# LED_String_NE2R757GT-P6.net
KiCad netlist of a schematic drawn in Altium Designer
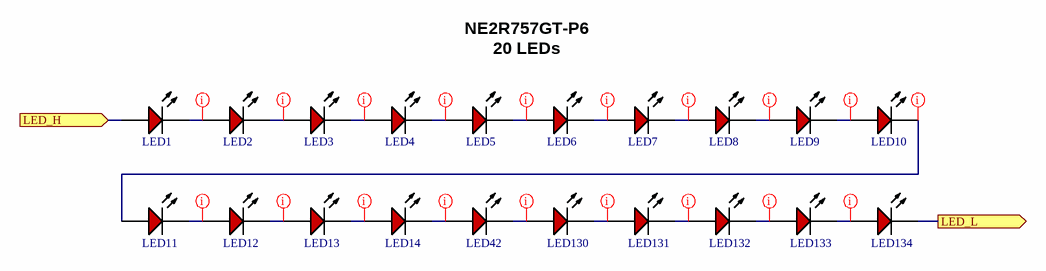
[diagram p0: LED_String_NE2R757GT-P6.SchDoc]

(export (version "E")
  (design (tool "Eeschema 10.0.6"))
  (components
    (comp (ref "LED1")
      (value "NE2R757GT-P6")
      (footprint "NE2R757GT-P6")
      (description "SMD LED Red 2,13 V, 16 lm 3030 (1212)")
      (fields (field (name "MANUFACTURER") "Nichia"))
      (libsource (lib "ETHZ Vault") (part "LED Red"))
    )
    (comp (ref "LED2")
      (value "NE2R757GT-P6")
      (footprint "NE2R757GT-P6")
      (description "SMD LED Red 2,13 V, 16 lm 3030 (1212)")
      (fields (field (name "MANUFACTURER") "Nichia"))
      (libsource (lib "ETHZ Vault") (part "LED Red"))
    )
    (comp (ref "LED3")
      (value "NE2R757GT-P6")
      (footprint "NE2R757GT-P6")
      (description "SMD LED Red 2,13 V, 16 lm 3030 (1212)")
      (fields (field (name "MANUFACTURER") "Nichia"))
      (libsource (lib "ETHZ Vault") (part "LED Red"))
    )
    (comp (ref "LED4")
      (value "NE2R757GT-P6")
      (footprint "NE2R757GT-P6")
      (description "SMD LED Red 2,13 V, 16 lm 3030 (1212)")
      (fields (field (name "MANUFACTURER") "Nichia"))
      (libsource (lib "ETHZ Vault") (part "LED Red"))
    )
    (comp (ref "LED5")
      (value "NE2R757GT-P6")
      (footprint "NE2R757GT-P6")
      (description "SMD LED Red 2,13 V, 16 lm 3030 (1212)")
      (fields (field (name "MANUFACTURER") "Nichia"))
      (libsource (lib "ETHZ Vault") (part "LED Red"))
    )
    (comp (ref "LED6")
      (value "NE2R757GT-P6")
      (footprint "NE2R757GT-P6")
      (description "SMD LED Red 2,13 V, 16 lm 3030 (1212)")
      (fields (field (name "MANUFACTURER") "Nichia"))
      (libsource (lib "ETHZ Vault") (part "LED Red"))
    )
    (comp (ref "LED7")
      (value "NE2R757GT-P6")
      (footprint "NE2R757GT-P6")
      (description "SMD LED Red 2,13 V, 16 lm 3030 (1212)")
      (fields (field (name "MANUFACTURER") "Nichia"))
      (libsource (lib "ETHZ Vault") (part "LED Red"))
    )
    (comp (ref "LED8")
      (value "NE2R757GT-P6")
      (footprint "NE2R757GT-P6")
      (description "SMD LED Red 2,13 V, 16 lm 3030 (1212)")
      (fields (field (name "MANUFACTURER") "Nichia"))
      (libsource (lib "ETHZ Vault") (part "LED Red"))
    )
    (comp (ref "LED9")
      (value "NE2R757GT-P6")
      (footprint "NE2R757GT-P6")
      (description "SMD LED Red 2,13 V, 16 lm 3030 (1212)")
      (fields (field (name "MANUFACTURER") "Nichia"))
      (libsource (lib "ETHZ Vault") (part "LED Red"))
    )
    (comp (ref "LED10")
      (value "NE2R757GT-P6")
      (footprint "NE2R757GT-P6")
      (description "SMD LED Red 2,13 V, 16 lm 3030 (1212)")
      (fields (field (name "MANUFACTURER") "Nichia"))
      (libsource (lib "ETHZ Vault") (part "LED Red"))
    )
    (comp (ref "LED11")
      (value "NE2R757GT-P6")
      (footprint "NE2R757GT-P6")
      (description "SMD LED Red 2,13 V, 16 lm 3030 (1212)")
      (fields (field (name "MANUFACTURER") "Nichia"))
      (libsource (lib "ETHZ Vault") (part "LED Red"))
    )
    (comp (ref "LED12")
      (value "NE2R757GT-P6")
      (footprint "NE2R757GT-P6")
      (description "SMD LED Red 2,13 V, 16 lm 3030 (1212)")
      (fields (field (name "MANUFACTURER") "Nichia"))
      (libsource (lib "ETHZ Vault") (part "LED Red"))
    )
    (comp (ref "LED13")
      (value "NE2R757GT-P6")
      (footprint "NE2R757GT-P6")
      (description "SMD LED Red 2,13 V, 16 lm 3030 (1212)")
      (fields (field (name "MANUFACTURER") "Nichia"))
      (libsource (lib "ETHZ Vault") (part "LED Red"))
    )
    (comp (ref "LED14")
      (value "NE2R757GT-P6")
      (footprint "NE2R757GT-P6")
      (description "SMD LED Red 2,13 V, 16 lm 3030 (1212)")
      (fields (field (name "MANUFACTURER") "Nichia"))
      (libsource (lib "ETHZ Vault") (part "LED Red"))
    )
    (comp (ref "LED42")
      (value "NE2R757GT-P6")
      (footprint "NE2R757GT-P6")
      (description "SMD LED Red 2,13 V, 16 lm 3030 (1212)")
      (fields (field (name "MANUFACTURER") "Nichia"))
      (libsource (lib "ETHZ Vault") (part "LED Red"))
    )
    (comp (ref "LED130")
      (value "NE2R757GT-P6")
      (footprint "NE2R757GT-P6")
      (description "SMD LED Red 2,13 V, 16 lm 3030 (1212)")
      (fields (field (name "MANUFACTURER") "Nichia"))
      (libsource (lib "ETHZ Vault") (part "LED Red"))
    )
    (comp (ref "LED131")
      (value "NE2R757GT-P6")
      (footprint "NE2R757GT-P6")
      (description "SMD LED Red 2,13 V, 16 lm 3030 (1212)")
      (fields (field (name "MANUFACTURER") "Nichia"))
      (libsource (lib "ETHZ Vault") (part "LED Red"))
    )
    (comp (ref "LED132")
      (value "NE2R757GT-P6")
      (footprint "NE2R757GT-P6")
      (description "SMD LED Red 2,13 V, 16 lm 3030 (1212)")
      (fields (field (name "MANUFACTURER") "Nichia"))
      (libsource (lib "ETHZ Vault") (part "LED Red"))
    )
    (comp (ref "LED133")
      (value "NE2R757GT-P6")
      (footprint "NE2R757GT-P6")
      (description "SMD LED Red 2,13 V, 16 lm 3030 (1212)")
      (fields (field (name "MANUFACTURER") "Nichia"))
      (libsource (lib "ETHZ Vault") (part "LED Red"))
    )
    (comp (ref "LED134")
      (value "NE2R757GT-P6")
      (footprint "NE2R757GT-P6")
      (description "SMD LED Red 2,13 V, 16 lm 3030 (1212)")
      (fields (field (name "MANUFACTURER") "Nichia"))
      (libsource (lib "ETHZ Vault") (part "LED Red"))
    )
  )
  (nets
    (net (code "1") (name "/LED_H") (class "Default")
      (node (ref "LED1") (pin "2") (pinfunction "A_2") (pintype "passive"))
    )
    (net (code "2") (name "/LED_L") (class "Default")
      (node (ref "LED134") (pin "1") (pinfunction "K_1") (pintype "passive"))
    )
    (net (code "3") (name "Net-(LED1-K)") (class "Default")
      (node (ref "LED1") (pin "1") (pinfunction "K_1") (pintype "passive"))
      (node (ref "LED2") (pin "2") (pinfunction "A_2") (pintype "passive"))
    )
    (net (code "4") (name "Net-(LED2-K)") (class "Default")
      (node (ref "LED2") (pin "1") (pinfunction "K_1") (pintype "passive"))
      (node (ref "LED3") (pin "2") (pinfunction "A_2") (pintype "passive"))
    )
    (net (code "5") (name "Net-(LED3-K)") (class "Default")
      (node (ref "LED3") (pin "1") (pinfunction "K_1") (pintype "passive"))
      (node (ref "LED4") (pin "2") (pinfunction "A_2") (pintype "passive"))
    )
    (net (code "6") (name "Net-(LED4-K)") (class "Default")
      (node (ref "LED4") (pin "1") (pinfunction "K_1") (pintype "passive"))
      (node (ref "LED5") (pin "2") (pinfunction "A_2") (pintype "passive"))
    )
    (net (code "7") (name "Net-(LED5-K)") (class "Default")
      (node (ref "LED5") (pin "1") (pinfunction "K_1") (pintype "passive"))
      (node (ref "LED6") (pin "2") (pinfunction "A_2") (pintype "passive"))
    )
    (net (code "8") (name "Net-(LED6-K)") (class "Default")
      (node (ref "LED6") (pin "1") (pinfunction "K_1") (pintype "passive"))
      (node (ref "LED7") (pin "2") (pinfunction "A_2") (pintype "passive"))
    )
    (net (code "9") (name "Net-(LED7-K)") (class "Default")
      (node (ref "LED7") (pin "1") (pinfunction "K_1") (pintype "passive"))
      (node (ref "LED8") (pin "2") (pinfunction "A_2") (pintype "passive"))
    )
    (net (code "10") (name "Net-(LED8-K)") (class "Default")
      (node (ref "LED8") (pin "1") (pinfunction "K_1") (pintype "passive"))
      (node (ref "LED9") (pin "2") (pinfunction "A_2") (pintype "passive"))
    )
    (net (code "11") (name "Net-(LED10-A)") (class "Default")
      (node (ref "LED10") (pin "2") (pinfunction "A_2") (pintype "passive"))
      (node (ref "LED9") (pin "1") (pinfunction "K_1") (pintype "passive"))
    )
    (net (code "12") (name "Net-(LED10-K)") (class "Default")
      (node (ref "LED10") (pin "1") (pinfunction "K_1") (pintype "passive"))
      (node (ref "LED11") (pin "2") (pinfunction "A_2") (pintype "passive"))
    )
    (net (code "13") (name "Net-(LED11-K)") (class "Default")
      (node (ref "LED11") (pin "1") (pinfunction "K_1") (pintype "passive"))
      (node (ref "LED12") (pin "2") (pinfunction "A_2") (pintype "passive"))
    )
    (net (code "14") (name "Net-(LED12-K)") (class "Default")
      (node (ref "LED12") (pin "1") (pinfunction "K_1") (pintype "passive"))
      (node (ref "LED13") (pin "2") (pinfunction "A_2") (pintype "passive"))
    )
    (net (code "15") (name "Net-(LED13-K)") (class "Default")
      (node (ref "LED13") (pin "1") (pinfunction "K_1") (pintype "passive"))
      (node (ref "LED14") (pin "2") (pinfunction "A_2") (pintype "passive"))
    )
    (net (code "16") (name "Net-(LED14-K)") (class "Default")
      (node (ref "LED14") (pin "1") (pinfunction "K_1") (pintype "passive"))
      (node (ref "LED42") (pin "2") (pinfunction "A_2") (pintype "passive"))
    )
    (net (code "17") (name "Net-(LED130-A)") (class "Default")
      (node (ref "LED130") (pin "2") (pinfunction "A_2") (pintype "passive"))
      (node (ref "LED42") (pin "1") (pinfunction "K_1") (pintype "passive"))
    )
    (net (code "18") (name "Net-(LED130-K)") (class "Default")
      (node (ref "LED130") (pin "1") (pinfunction "K_1") (pintype "passive"))
      (node (ref "LED131") (pin "2") (pinfunction "A_2") (pintype "passive"))
    )
    (net (code "19") (name "Net-(LED131-K)") (class "Default")
      (node (ref "LED131") (pin "1") (pinfunction "K_1") (pintype "passive"))
      (node (ref "LED132") (pin "2") (pinfunction "A_2") (pintype "passive"))
    )
    (net (code "20") (name "Net-(LED132-K)") (class "Default")
      (node (ref "LED132") (pin "1") (pinfunction "K_1") (pintype "passive"))
      (node (ref "LED133") (pin "2") (pinfunction "A_2") (pintype "passive"))
    )
    (net (code "21") (name "Net-(LED133-K)") (class "Default")
      (node (ref "LED133") (pin "1") (pinfunction "K_1") (pintype "passive"))
      (node (ref "LED134") (pin "2") (pinfunction "A_2") (pintype "passive"))
    )
  )
)
